# 3V-Switcher-50mA.net
KiCad netlist of a schematic drawn in Altium Designer
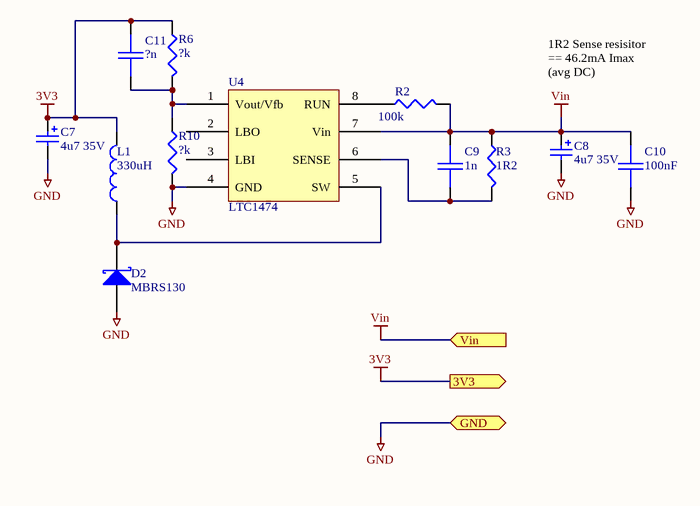
[diagram p0: 3V-Switcher-50mA.SCHDOC]

(export (version "E")
  (design (tool "Eeschema 10.0.6"))
  (components
    (comp (ref "C7")
      (value "4u7 35V")
      (footprint "MCCT-CASEC")
      (description "Polarized Capacitor (Surface Mount)")
      (libsource (lib "Miscellaneous Devices") (part "Cap Pol3"))
    )
    (comp (ref "C8")
      (value "4u7 35V")
      (footprint "MCCT-CASEC")
      (description "Polarized Capacitor (Surface Mount)")
      (libsource (lib "Miscellaneous Devices") (part "Cap Pol3"))
    )
    (comp (ref "C9")
      (value "1n")
      (footprint "0603")
      (description "Capacitor")
      (libsource (lib "Miscellaneous Devices") (part "CAP"))
    )
    (comp (ref "C10")
      (value "100nF")
      (footprint "0603")
      (description "Capacitor")
      (libsource (lib "Miscellaneous Devices") (part "CAP"))
    )
    (comp (ref "C11")
      (value "?n")
      (footprint "0603")
      (description "Capacitor")
      (libsource (lib "Miscellaneous Devices") (part "CAP"))
    )
    (comp (ref "D2")
      (value "MBRS130")
      (footprint "SMB")
      (description "Schottky Diode")
      (libsource (lib "RCLDQ") (part "D SCHOTTKY"))
    )
    (comp (ref "L1")
      (value "330uH")
      (footprint "1812")
      (description "Inductor")
      (libsource (lib "Miscellaneous Devices") (part "Inductor"))
    )
    (comp (ref "R2")
      (value "100k")
      (footprint "0603")
      (description "Resistor")
      (libsource (lib "RCLDQ") (part "RES1"))
    )
    (comp (ref "R3")
      (value "1R2")
      (footprint "0603")
      (description "Resistor")
      (libsource (lib "Miscellaneous Devices") (part "RES1"))
    )
    (comp (ref "R6")
      (value "?k")
      (footprint "0603")
      (description "Resistor")
      (fields (field (name "Comment") "100k"))
      (libsource (lib "RCLDQ") (part "RES1"))
    )
    (comp (ref "R10")
      (value "?k")
      (footprint "0603")
      (description "Resistor")
      (fields (field (name "Comment") "100k"))
      (libsource (lib "RCLDQ") (part "RES1"))
    )
    (comp (ref "U4")
      (value "LTC1474")
      (footprint "SO8")
      (description "Step-down converter")
      (libsource (lib "MiscellaneousIC") (part "LTC1474"))
    )
  )
  (nets
    (net (code "1") (name "3V3") (class "Default")
      (node (ref "C11") (pin "1") (pinfunction "1_1") (pintype "passive"))
      (node (ref "C7") (pin "1") (pinfunction "1_1") (pintype "passive"))
      (node (ref "L1") (pin "2") (pinfunction "2_2") (pintype "passive"))
      (node (ref "R6") (pin "1") (pinfunction "1_1") (pintype "passive"))
    )
    (net (code "2") (name "GND") (class "Default")
      (node (ref "C10") (pin "2") (pinfunction "2_2") (pintype "passive"))
      (node (ref "C7") (pin "2") (pinfunction "2_2") (pintype "passive"))
      (node (ref "C8") (pin "2") (pinfunction "2_2") (pintype "passive"))
      (node (ref "D2") (pin "A") (pinfunction "A_A") (pintype "passive"))
      (node (ref "R10") (pin "2") (pinfunction "2_2") (pintype "passive"))
      (node (ref "U4") (pin "4") (pinfunction "GND_4") (pintype "passive"))
    )
    (net (code "3") (name "Net-(U4-RUN)") (class "Default")
      (node (ref "R2") (pin "1") (pinfunction "1_1") (pintype "passive"))
      (node (ref "U4") (pin "8") (pinfunction "RUN_8") (pintype "passive"))
    )
    (net (code "4") (name "Net-(U4-SENSE)") (class "Default")
      (node (ref "C9") (pin "2") (pinfunction "2_2") (pintype "passive"))
      (node (ref "R3") (pin "2") (pinfunction "2_2") (pintype "passive"))
      (node (ref "U4") (pin "6") (pinfunction "SENSE_6") (pintype "passive"))
    )
    (net (code "5") (name "Net-(U4-SW)") (class "Default")
      (node (ref "D2") (pin "K") (pinfunction "K_K") (pintype "passive"))
      (node (ref "L1") (pin "1") (pinfunction "1_1") (pintype "passive"))
      (node (ref "U4") (pin "5") (pinfunction "SW_5") (pintype "passive"))
    )
    (net (code "6") (name "Net-(U4-Vout{slash}Vfb)") (class "Default")
      (node (ref "C11") (pin "2") (pinfunction "2_2") (pintype "passive"))
      (node (ref "R10") (pin "1") (pinfunction "1_1") (pintype "passive"))
      (node (ref "R6") (pin "2") (pinfunction "2_2") (pintype "passive"))
      (node (ref "U4") (pin "1") (pinfunction "Vout/Vfb_1") (pintype "passive"))
    )
    (net (code "7") (name "Vin") (class "Default")
      (node (ref "C10") (pin "1") (pinfunction "1_1") (pintype "passive"))
      (node (ref "C8") (pin "1") (pinfunction "1_1") (pintype "passive"))
      (node (ref "C9") (pin "1") (pinfunction "1_1") (pintype "passive"))
      (node (ref "R2") (pin "2") (pinfunction "2_2") (pintype "passive"))
      (node (ref "R3") (pin "1") (pinfunction "1_1") (pintype "passive"))
      (node (ref "U4") (pin "7") (pinfunction "Vin_7") (pintype "passive"))
    )
    (net (code "8") (name "unconnected-(U4-LBI-Pad3)") (class "Default")
      (node (ref "U4") (pin "3") (pinfunction "LBI_3") (pintype "passive"))
    )
    (net (code "9") (name "unconnected-(U4-LBO-Pad2)") (class "Default")
      (node (ref "U4") (pin "2") (pinfunction "LBO_2") (pintype "passive"))
    )
  )
)
